# Sensors.net
KiCad netlist of a schematic drawn in Altium Designer
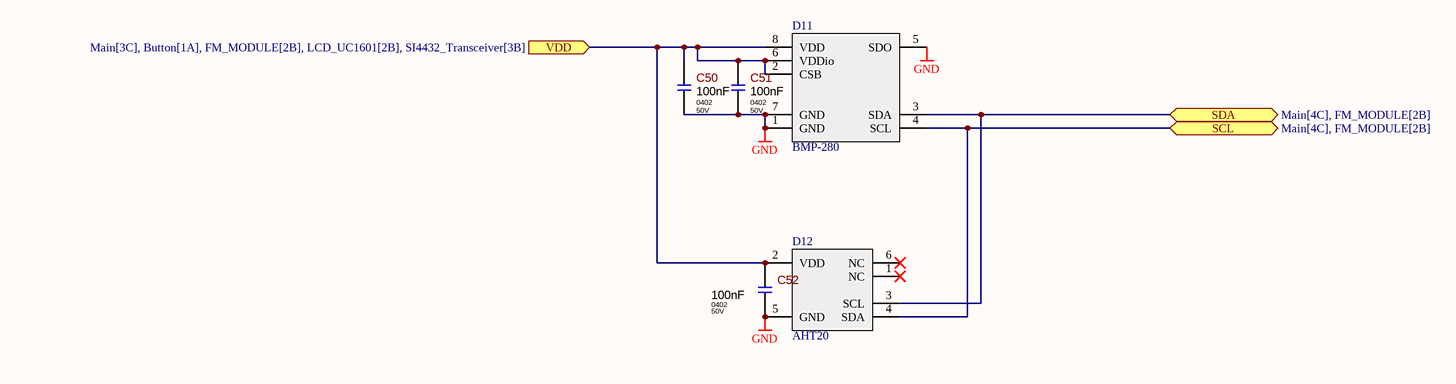
[diagram p0: Sensors.SchDoc]

(export (version "E")
  (design (tool "Eeschema 10.0.6"))
  (components
    (comp (ref "C50")
      (value "100nF")
      (footprint "Cap_0402")
      (description "100nF 50V  ±25% 0402 Ceramic Capacitor")
      (fields
        (field (name "TOLERANCE") "±25%")
        (field (name "PACKAGE") "0402")
        (field (name "VOLTAGE") "50V")
      )
      (libsource (lib "Capacitors") (part "Cap_0402_100nF"))
    )
    (comp (ref "C51")
      (value "100nF")
      (footprint "Cap_0402")
      (description "100nF 50V  ±25% 0402 Ceramic Capacitor")
      (fields
        (field (name "TOLERANCE") "±25%")
        (field (name "PACKAGE") "0402")
        (field (name "VOLTAGE") "50V")
      )
      (libsource (lib "Capacitors") (part "Cap_0402_100nF"))
    )
    (comp (ref "C52")
      (value "100nF")
      (footprint "Cap_0402")
      (description "100nF 50V  ±25% 0402 Ceramic Capacitor")
      (fields
        (field (name "TOLERANCE") "±25%")
        (field (name "PACKAGE") "0402")
        (field (name "VOLTAGE") "50V")
      )
      (libsource (lib "Capacitors") (part "Cap_0402_100nF"))
    )
    (comp (ref "D11") (value "BMP-280") (footprint "BMP-280") (libsource (lib "Sensors") (part "BMP-280")))
    (comp (ref "D12")
      (value "AHT20")
      (footprint "AHT20")
      (description "Temperature and humidity sensor -40+85 0-100%\r\n1.8-3.3v")
      (fields (field (name "NAME") "AHT20"))
      (libsource (lib "Sensors") (part "AHT20"))
    )
  )
  (nets
    (net (code "1") (name "/SCL") (class "Default")
      (node (ref "D11") (pin "4") (pinfunction "SCL_4") (pintype "passive"))
      (node (ref "D12") (pin "4") (pinfunction "SDA_4") (pintype "passive"))
    )
    (net (code "2") (name "/SDA") (class "Default")
      (node (ref "D11") (pin "3") (pinfunction "SDA_3") (pintype "passive"))
      (node (ref "D12") (pin "3") (pinfunction "SCL_3") (pintype "passive"))
    )
    (net (code "3") (name "/VDD") (class "Default")
      (node (ref "C50") (pin "1") (pinfunction "1_1") (pintype "passive"))
      (node (ref "C51") (pin "1") (pinfunction "1_1") (pintype "passive"))
      (node (ref "C52") (pin "1") (pinfunction "1_1") (pintype "passive"))
      (node (ref "D11") (pin "2") (pinfunction "CSB_2") (pintype "passive"))
      (node (ref "D11") (pin "6") (pinfunction "VDDio_6") (pintype "passive"))
      (node (ref "D11") (pin "8") (pinfunction "VDD_8") (pintype "passive"))
      (node (ref "D12") (pin "2") (pinfunction "VDD_2") (pintype "passive"))
    )
    (net (code "4") (name "GND") (class "Default")
      (node (ref "C50") (pin "2") (pinfunction "2_2") (pintype "passive"))
      (node (ref "C51") (pin "2") (pinfunction "2_2") (pintype "passive"))
      (node (ref "C52") (pin "2") (pinfunction "2_2") (pintype "passive"))
      (node (ref "D11") (pin "1") (pinfunction "GND_1") (pintype "passive"))
      (node (ref "D11") (pin "5") (pinfunction "SDO_5") (pintype "passive"))
      (node (ref "D11") (pin "7") (pinfunction "GND_7") (pintype "passive"))
      (node (ref "D12") (pin "5") (pinfunction "GND_5") (pintype "passive"))
    )
    (net (code "5") (name "unconnected-(D12-NC-Pad1)") (class "Default")
      (node (ref "D12") (pin "1") (pinfunction "NC_1") (pintype "passive+no_connect"))
    )
    (net (code "6") (name "unconnected-(D12-NC-Pad6)") (class "Default")
      (node (ref "D12") (pin "6") (pinfunction "NC_6") (pintype "passive+no_connect"))
    )
  )
)
